# GPIO_interface.net
KiCad netlist of a schematic drawn in EAGLE
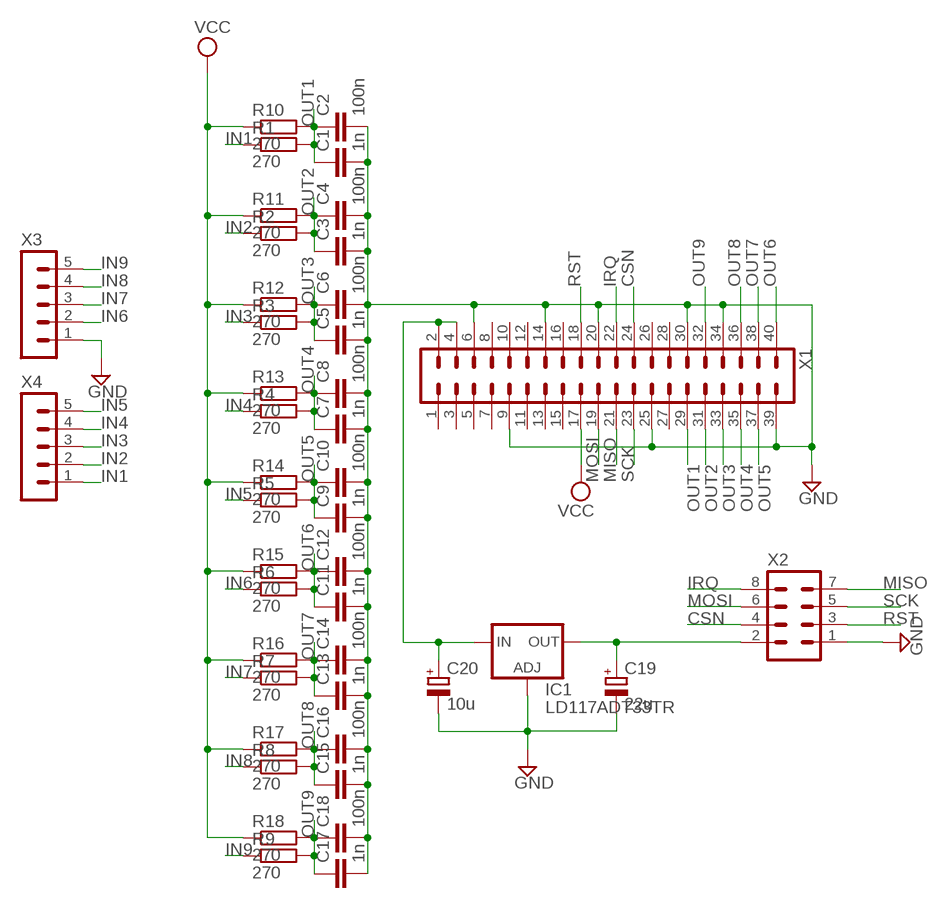
[diagram p0: schematic, sheet 1]

(export (version "E")
  (design (tool "Eeschema 10.0.6"))
  (components
    (comp (ref "C1")
      (value "1n")
      (footprint "eagle-import:C0603")
      (libsource (lib "eagle-import") (part "C-EUC0603"))
    )
    (comp (ref "C2")
      (value "100n")
      (footprint "eagle-import:C0603")
      (libsource (lib "eagle-import") (part "C-EUC0603"))
    )
    (comp (ref "C3")
      (value "1n")
      (footprint "eagle-import:C0603")
      (libsource (lib "eagle-import") (part "C-EUC0603"))
    )
    (comp (ref "C4")
      (value "100n")
      (footprint "eagle-import:C0603")
      (libsource (lib "eagle-import") (part "C-EUC0603"))
    )
    (comp (ref "C5")
      (value "1n")
      (footprint "eagle-import:C0603")
      (libsource (lib "eagle-import") (part "C-EUC0603"))
    )
    (comp (ref "C6")
      (value "100n")
      (footprint "eagle-import:C0603")
      (libsource (lib "eagle-import") (part "C-EUC0603"))
    )
    (comp (ref "C7")
      (value "1n")
      (footprint "eagle-import:C0603")
      (libsource (lib "eagle-import") (part "C-EUC0603"))
    )
    (comp (ref "C8")
      (value "100n")
      (footprint "eagle-import:C0603")
      (libsource (lib "eagle-import") (part "C-EUC0603"))
    )
    (comp (ref "C9")
      (value "1n")
      (footprint "eagle-import:C0603")
      (libsource (lib "eagle-import") (part "C-EUC0603"))
    )
    (comp (ref "C10")
      (value "100n")
      (footprint "eagle-import:C0603")
      (libsource (lib "eagle-import") (part "C-EUC0603"))
    )
    (comp (ref "C11")
      (value "1n")
      (footprint "eagle-import:C0603")
      (libsource (lib "eagle-import") (part "C-EUC0603"))
    )
    (comp (ref "C12")
      (value "100n")
      (footprint "eagle-import:C0603")
      (libsource (lib "eagle-import") (part "C-EUC0603"))
    )
    (comp (ref "C13")
      (value "1n")
      (footprint "eagle-import:C0603")
      (libsource (lib "eagle-import") (part "C-EUC0603"))
    )
    (comp (ref "C14")
      (value "100n")
      (footprint "eagle-import:C0603")
      (libsource (lib "eagle-import") (part "C-EUC0603"))
    )
    (comp (ref "C15")
      (value "1n")
      (footprint "eagle-import:C0603")
      (libsource (lib "eagle-import") (part "C-EUC0603"))
    )
    (comp (ref "C16")
      (value "100n")
      (footprint "eagle-import:C0603")
      (libsource (lib "eagle-import") (part "C-EUC0603"))
    )
    (comp (ref "C17")
      (value "1n")
      (footprint "eagle-import:C0603")
      (libsource (lib "eagle-import") (part "C-EUC0603"))
    )
    (comp (ref "C18")
      (value "100n")
      (footprint "eagle-import:C0603")
      (libsource (lib "eagle-import") (part "C-EUC0603"))
    )
    (comp (ref "C19")
      (value "22u")
      (footprint "eagle-import:C_6032-28R")
      (libsource (lib "eagle-import") (part "CPOL-EUC/6032-28R"))
    )
    (comp (ref "C20")
      (value "10u")
      (footprint "eagle-import:C_6032-28R")
      (libsource (lib "eagle-import") (part "CPOL-EUC/6032-28R"))
    )
    (comp (ref "IC1")
      (value "LD117ADT33TR")
      (footprint "eagle-import:DPACK")
      (libsource (lib "eagle-import") (part "LD117A?DT33TR"))
    )
    (comp (ref "R1")
      (value "270")
      (footprint "eagle-import:R0603")
      (libsource (lib "eagle-import") (part "R-EU_R0603"))
    )
    (comp (ref "R2")
      (value "270")
      (footprint "eagle-import:R0603")
      (libsource (lib "eagle-import") (part "R-EU_R0603"))
    )
    (comp (ref "R3")
      (value "270")
      (footprint "eagle-import:R0603")
      (libsource (lib "eagle-import") (part "R-EU_R0603"))
    )
    (comp (ref "R4")
      (value "270")
      (footprint "eagle-import:R0603")
      (libsource (lib "eagle-import") (part "R-EU_R0603"))
    )
    (comp (ref "R5")
      (value "270")
      (footprint "eagle-import:R0603")
      (libsource (lib "eagle-import") (part "R-EU_R0603"))
    )
    (comp (ref "R6")
      (value "270")
      (footprint "eagle-import:R0603")
      (libsource (lib "eagle-import") (part "R-EU_R0603"))
    )
    (comp (ref "R7")
      (value "270")
      (footprint "eagle-import:R0603")
      (libsource (lib "eagle-import") (part "R-EU_R0603"))
    )
    (comp (ref "R8")
      (value "270")
      (footprint "eagle-import:R0603")
      (libsource (lib "eagle-import") (part "R-EU_R0603"))
    )
    (comp (ref "R9")
      (value "270")
      (footprint "eagle-import:R0603")
      (libsource (lib "eagle-import") (part "R-EU_R0603"))
    )
    (comp (ref "R10")
      (value "270")
      (footprint "eagle-import:R0603")
      (libsource (lib "eagle-import") (part "R-EU_R0603"))
    )
    (comp (ref "R11")
      (value "270")
      (footprint "eagle-import:R0603")
      (libsource (lib "eagle-import") (part "R-EU_R0603"))
    )
    (comp (ref "R12")
      (value "270")
      (footprint "eagle-import:R0603")
      (libsource (lib "eagle-import") (part "R-EU_R0603"))
    )
    (comp (ref "R13")
      (value "270")
      (footprint "eagle-import:R0603")
      (libsource (lib "eagle-import") (part "R-EU_R0603"))
    )
    (comp (ref "R14")
      (value "270")
      (footprint "eagle-import:R0603")
      (libsource (lib "eagle-import") (part "R-EU_R0603"))
    )
    (comp (ref "R15")
      (value "270")
      (footprint "eagle-import:R0603")
      (libsource (lib "eagle-import") (part "R-EU_R0603"))
    )
    (comp (ref "R16")
      (value "270")
      (footprint "eagle-import:R0603")
      (libsource (lib "eagle-import") (part "R-EU_R0603"))
    )
    (comp (ref "R17")
      (value "270")
      (footprint "eagle-import:R0603")
      (libsource (lib "eagle-import") (part "R-EU_R0603"))
    )
    (comp (ref "R18")
      (value "270")
      (footprint "eagle-import:R0603")
      (libsource (lib "eagle-import") (part "R-EU_R0603"))
    )
    (comp (ref "X1")
      (value "MA20-2")
      (footprint "eagle-import:MA20-2")
      (libsource (lib "eagle-import") (part "MA20-2"))
    )
    (comp (ref "X2")
      (value "MA04-2")
      (footprint "eagle-import:MA04-2")
      (libsource (lib "eagle-import") (part "MA04-2"))
    )
    (comp (ref "X3")
      (value "MA05-1")
      (footprint "eagle-import:MA05-1")
      (libsource (lib "eagle-import") (part "MA05-1"))
    )
    (comp (ref "X4")
      (value "MA05-1")
      (footprint "eagle-import:MA05-1")
      (libsource (lib "eagle-import") (part "MA05-1"))
    )
  )
  (nets
    (net (code "1") (name "/CSN") (class "Default")
      (node (ref "X1") (pin "24") (pinfunction "24_24") (pintype "passive"))
      (node (ref "X2") (pin "4") (pinfunction "4_4") (pintype "passive"))
    )
    (net (code "2") (name "/IN1") (class "Default")
      (node (ref "R1") (pin "1") (pinfunction "1_1") (pintype "passive"))
      (node (ref "X4") (pin "1") (pinfunction "1_1") (pintype "passive"))
    )
    (net (code "3") (name "/IN2") (class "Default")
      (node (ref "R2") (pin "1") (pinfunction "1_1") (pintype "passive"))
      (node (ref "X4") (pin "2") (pinfunction "2_2") (pintype "passive"))
    )
    (net (code "4") (name "/IN3") (class "Default")
      (node (ref "R3") (pin "1") (pinfunction "1_1") (pintype "passive"))
      (node (ref "X4") (pin "3") (pinfunction "3_3") (pintype "passive"))
    )
    (net (code "5") (name "/IN4") (class "Default")
      (node (ref "R4") (pin "1") (pinfunction "1_1") (pintype "passive"))
      (node (ref "X4") (pin "4") (pinfunction "4_4") (pintype "passive"))
    )
    (net (code "6") (name "/IN5") (class "Default")
      (node (ref "R5") (pin "1") (pinfunction "1_1") (pintype "passive"))
      (node (ref "X4") (pin "5") (pinfunction "5_5") (pintype "passive"))
    )
    (net (code "7") (name "/IN6") (class "Default")
      (node (ref "R6") (pin "1") (pinfunction "1_1") (pintype "passive"))
      (node (ref "X3") (pin "2") (pinfunction "2_2") (pintype "passive"))
    )
    (net (code "8") (name "/IN7") (class "Default")
      (node (ref "R7") (pin "1") (pinfunction "1_1") (pintype "passive"))
      (node (ref "X3") (pin "3") (pinfunction "3_3") (pintype "passive"))
    )
    (net (code "9") (name "/IN8") (class "Default")
      (node (ref "R8") (pin "1") (pinfunction "1_1") (pintype "passive"))
      (node (ref "X3") (pin "4") (pinfunction "4_4") (pintype "passive"))
    )
    (net (code "10") (name "/IN9") (class "Default")
      (node (ref "R9") (pin "1") (pinfunction "1_1") (pintype "passive"))
      (node (ref "X3") (pin "5") (pinfunction "5_5") (pintype "passive"))
    )
    (net (code "11") (name "/IRQ") (class "Default")
      (node (ref "X1") (pin "22") (pinfunction "22_22") (pintype "passive"))
      (node (ref "X2") (pin "8") (pinfunction "8_8") (pintype "passive"))
    )
    (net (code "12") (name "/MISO") (class "Default")
      (node (ref "X1") (pin "21") (pinfunction "21_21") (pintype "passive"))
      (node (ref "X2") (pin "7") (pinfunction "7_7") (pintype "passive"))
    )
    (net (code "13") (name "/MOSI") (class "Default")
      (node (ref "X1") (pin "19") (pinfunction "19_19") (pintype "passive"))
      (node (ref "X2") (pin "6") (pinfunction "6_6") (pintype "passive"))
    )
    (net (code "14") (name "/OUT1") (class "Default")
      (node (ref "C1") (pin "1") (pinfunction "1_1") (pintype "passive"))
      (node (ref "C2") (pin "1") (pinfunction "1_1") (pintype "passive"))
      (node (ref "R1") (pin "2") (pinfunction "2_2") (pintype "passive"))
      (node (ref "R10") (pin "2") (pinfunction "2_2") (pintype "passive"))
      (node (ref "X1") (pin "29") (pinfunction "29_29") (pintype "passive"))
    )
    (net (code "15") (name "/OUT2") (class "Default")
      (node (ref "C3") (pin "1") (pinfunction "1_1") (pintype "passive"))
      (node (ref "C4") (pin "1") (pinfunction "1_1") (pintype "passive"))
      (node (ref "R11") (pin "2") (pinfunction "2_2") (pintype "passive"))
      (node (ref "R2") (pin "2") (pinfunction "2_2") (pintype "passive"))
      (node (ref "X1") (pin "31") (pinfunction "31_31") (pintype "passive"))
    )
    (net (code "16") (name "/OUT3") (class "Default")
      (node (ref "C5") (pin "1") (pinfunction "1_1") (pintype "passive"))
      (node (ref "C6") (pin "1") (pinfunction "1_1") (pintype "passive"))
      (node (ref "R12") (pin "2") (pinfunction "2_2") (pintype "passive"))
      (node (ref "R3") (pin "2") (pinfunction "2_2") (pintype "passive"))
      (node (ref "X1") (pin "33") (pinfunction "33_33") (pintype "passive"))
    )
    (net (code "17") (name "/OUT4") (class "Default")
      (node (ref "C7") (pin "1") (pinfunction "1_1") (pintype "passive"))
      (node (ref "C8") (pin "1") (pinfunction "1_1") (pintype "passive"))
      (node (ref "R13") (pin "2") (pinfunction "2_2") (pintype "passive"))
      (node (ref "R4") (pin "2") (pinfunction "2_2") (pintype "passive"))
      (node (ref "X1") (pin "35") (pinfunction "35_35") (pintype "passive"))
    )
    (net (code "18") (name "/OUT5") (class "Default")
      (node (ref "C10") (pin "1") (pinfunction "1_1") (pintype "passive"))
      (node (ref "C9") (pin "1") (pinfunction "1_1") (pintype "passive"))
      (node (ref "R14") (pin "2") (pinfunction "2_2") (pintype "passive"))
      (node (ref "R5") (pin "2") (pinfunction "2_2") (pintype "passive"))
      (node (ref "X1") (pin "37") (pinfunction "37_37") (pintype "passive"))
    )
    (net (code "19") (name "/OUT6") (class "Default")
      (node (ref "C11") (pin "1") (pinfunction "1_1") (pintype "passive"))
      (node (ref "C12") (pin "1") (pinfunction "1_1") (pintype "passive"))
      (node (ref "R15") (pin "2") (pinfunction "2_2") (pintype "passive"))
      (node (ref "R6") (pin "2") (pinfunction "2_2") (pintype "passive"))
      (node (ref "X1") (pin "40") (pinfunction "40_40") (pintype "passive"))
    )
    (net (code "20") (name "/OUT7") (class "Default")
      (node (ref "C13") (pin "1") (pinfunction "1_1") (pintype "passive"))
      (node (ref "C14") (pin "1") (pinfunction "1_1") (pintype "passive"))
      (node (ref "R16") (pin "2") (pinfunction "2_2") (pintype "passive"))
      (node (ref "R7") (pin "2") (pinfunction "2_2") (pintype "passive"))
      (node (ref "X1") (pin "38") (pinfunction "38_38") (pintype "passive"))
    )
    (net (code "21") (name "/OUT8") (class "Default")
      (node (ref "C15") (pin "1") (pinfunction "1_1") (pintype "passive"))
      (node (ref "C16") (pin "1") (pinfunction "1_1") (pintype "passive"))
      (node (ref "R17") (pin "2") (pinfunction "2_2") (pintype "passive"))
      (node (ref "R8") (pin "2") (pinfunction "2_2") (pintype "passive"))
      (node (ref "X1") (pin "36") (pinfunction "36_36") (pintype "passive"))
    )
    (net (code "22") (name "/OUT9") (class "Default")
      (node (ref "C17") (pin "1") (pinfunction "1_1") (pintype "passive"))
      (node (ref "C18") (pin "1") (pinfunction "1_1") (pintype "passive"))
      (node (ref "R18") (pin "2") (pinfunction "2_2") (pintype "passive"))
      (node (ref "R9") (pin "2") (pinfunction "2_2") (pintype "passive"))
      (node (ref "X1") (pin "32") (pinfunction "32_32") (pintype "passive"))
    )
    (net (code "23") (name "/RST") (class "Default")
      (node (ref "X1") (pin "18") (pinfunction "18_18") (pintype "passive"))
      (node (ref "X2") (pin "3") (pinfunction "3_3") (pintype "passive"))
    )
    (net (code "24") (name "/SCK") (class "Default")
      (node (ref "X1") (pin "23") (pinfunction "23_23") (pintype "passive"))
      (node (ref "X2") (pin "5") (pinfunction "5_5") (pintype "passive"))
    )
    (net (code "25") (name "GND") (class "Default")
      (node (ref "C1") (pin "2") (pinfunction "2_2") (pintype "passive"))
      (node (ref "C10") (pin "2") (pinfunction "2_2") (pintype "passive"))
      (node (ref "C11") (pin "2") (pinfunction "2_2") (pintype "passive"))
      (node (ref "C12") (pin "2") (pinfunction "2_2") (pintype "passive"))
      (node (ref "C13") (pin "2") (pinfunction "2_2") (pintype "passive"))
      (node (ref "C14") (pin "2") (pinfunction "2_2") (pintype "passive"))
      (node (ref "C15") (pin "2") (pinfunction "2_2") (pintype "passive"))
      (node (ref "C16") (pin "2") (pinfunction "2_2") (pintype "passive"))
      (node (ref "C17") (pin "2") (pinfunction "2_2") (pintype "passive"))
      (node (ref "C18") (pin "2") (pinfunction "2_2") (pintype "passive"))
      (node (ref "C19") (pin "-") (pinfunction "-_-") (pintype "passive"))
      (node (ref "C2") (pin "2") (pinfunction "2_2") (pintype "passive"))
      (node (ref "C20") (pin "-") (pinfunction "-_-") (pintype "passive"))
      (node (ref "C3") (pin "2") (pinfunction "2_2") (pintype "passive"))
      (node (ref "C4") (pin "2") (pinfunction "2_2") (pintype "passive"))
      (node (ref "C5") (pin "2") (pinfunction "2_2") (pintype "passive"))
      (node (ref "C6") (pin "2") (pinfunction "2_2") (pintype "passive"))
      (node (ref "C7") (pin "2") (pinfunction "2_2") (pintype "passive"))
      (node (ref "C8") (pin "2") (pinfunction "2_2") (pintype "passive"))
      (node (ref "C9") (pin "2") (pinfunction "2_2") (pintype "passive"))
      (node (ref "IC1") (pin "1") (pinfunction "ADJ_1") (pintype "input"))
      (node (ref "X1") (pin "14") (pinfunction "14_14") (pintype "passive"))
      (node (ref "X1") (pin "20") (pinfunction "20_20") (pintype "passive"))
      (node (ref "X1") (pin "25") (pinfunction "25_25") (pintype "passive"))
      (node (ref "X1") (pin "30") (pinfunction "30_30") (pintype "passive"))
      (node (ref "X1") (pin "34") (pinfunction "34_34") (pintype "passive"))
      (node (ref "X1") (pin "39") (pinfunction "39_39") (pintype "passive"))
      (node (ref "X1") (pin "6") (pinfunction "6_6") (pintype "passive"))
      (node (ref "X1") (pin "9") (pinfunction "9_9") (pintype "passive"))
      (node (ref "X2") (pin "1") (pinfunction "1_1") (pintype "passive"))
      (node (ref "X3") (pin "1") (pinfunction "1_1") (pintype "passive"))
    )
    (net (code "26") (name "Net-(IC1-IN)") (class "Default")
      (node (ref "C20") (pin "+") (pinfunction "+_+") (pintype "passive"))
      (node (ref "IC1") (pin "3") (pinfunction "IN_3") (pintype "input"))
      (node (ref "X1") (pin "2") (pinfunction "2_2") (pintype "passive"))
      (node (ref "X1") (pin "4") (pinfunction "4_4") (pintype "passive"))
    )
    (net (code "27") (name "Net-(IC1-OUT)") (class "Default")
      (node (ref "C19") (pin "+") (pinfunction "+_+") (pintype "passive"))
      (node (ref "IC1") (pin "4") (pinfunction "OUT_4") (pintype "passive"))
      (node (ref "X2") (pin "2") (pinfunction "2_2") (pintype "passive"))
    )
    (net (code "28") (name "VCC") (class "Default")
      (node (ref "R10") (pin "1") (pinfunction "1_1") (pintype "passive"))
      (node (ref "R11") (pin "1") (pinfunction "1_1") (pintype "passive"))
      (node (ref "R12") (pin "1") (pinfunction "1_1") (pintype "passive"))
      (node (ref "R13") (pin "1") (pinfunction "1_1") (pintype "passive"))
      (node (ref "R14") (pin "1") (pinfunction "1_1") (pintype "passive"))
      (node (ref "R15") (pin "1") (pinfunction "1_1") (pintype "passive"))
      (node (ref "R16") (pin "1") (pinfunction "1_1") (pintype "passive"))
      (node (ref "R17") (pin "1") (pinfunction "1_1") (pintype "passive"))
      (node (ref "R18") (pin "1") (pinfunction "1_1") (pintype "passive"))
      (node (ref "X1") (pin "17") (pinfunction "17_17") (pintype "passive"))
    )
    (net (code "29") (name "unconnected-(X1-Pad1)") (class "Default")
      (node (ref "X1") (pin "1") (pinfunction "1_1") (pintype "passive"))
    )
    (net (code "30") (name "unconnected-(X1-Pad3)") (class "Default")
      (node (ref "X1") (pin "3") (pinfunction "3_3") (pintype "passive"))
    )
    (net (code "31") (name "unconnected-(X1-Pad5)") (class "Default")
      (node (ref "X1") (pin "5") (pinfunction "5_5") (pintype "passive"))
    )
    (net (code "32") (name "unconnected-(X1-Pad7)") (class "Default")
      (node (ref "X1") (pin "7") (pinfunction "7_7") (pintype "passive"))
    )
    (net (code "33") (name "unconnected-(X1-Pad8)") (class "Default")
      (node (ref "X1") (pin "8") (pinfunction "8_8") (pintype "passive"))
    )
    (net (code "34") (name "unconnected-(X1-Pad10)") (class "Default")
      (node (ref "X1") (pin "10") (pinfunction "10_10") (pintype "passive"))
    )
    (net (code "35") (name "unconnected-(X1-Pad11)") (class "Default")
      (node (ref "X1") (pin "11") (pinfunction "11_11") (pintype "passive"))
    )
    (net (code "36") (name "unconnected-(X1-Pad12)") (class "Default")
      (node (ref "X1") (pin "12") (pinfunction "12_12") (pintype "passive"))
    )
    (net (code "37") (name "unconnected-(X1-Pad13)") (class "Default")
      (node (ref "X1") (pin "13") (pinfunction "13_13") (pintype "passive"))
    )
    (net (code "38") (name "unconnected-(X1-Pad15)") (class "Default")
      (node (ref "X1") (pin "15") (pinfunction "15_15") (pintype "passive"))
    )
    (net (code "39") (name "unconnected-(X1-Pad16)") (class "Default")
      (node (ref "X1") (pin "16") (pinfunction "16_16") (pintype "passive"))
    )
    (net (code "40") (name "unconnected-(X1-Pad26)") (class "Default")
      (node (ref "X1") (pin "26") (pinfunction "26_26") (pintype "passive"))
    )
    (net (code "41") (name "unconnected-(X1-Pad27)") (class "Default")
      (node (ref "X1") (pin "27") (pinfunction "27_27") (pintype "passive"))
    )
    (net (code "42") (name "unconnected-(X1-Pad28)") (class "Default")
      (node (ref "X1") (pin "28") (pinfunction "28_28") (pintype "passive"))
    )
  )
)
